# motor.net
KiCad netlist of a schematic drawn in EAGLE
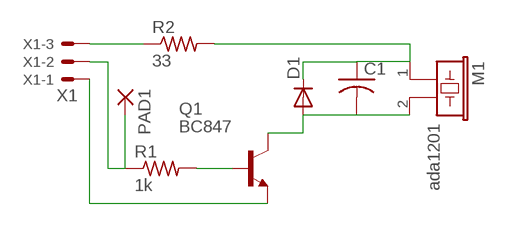
[diagram p0: schematic, sheet 1]

(export (version "E")
  (design (tool "Eeschema 10.0.6"))
  (components
    (comp (ref "C1")
      (value "C-USC0603")
      (footprint "eagle-import:C0603")
      (libsource (lib "eagle-import") (part "C-USC0603"))
    )
    (comp (ref "D1")
      (value "DIODE-DO214AC")
      (footprint "eagle-import:DO214AC")
      (libsource (lib "eagle-import") (part "DIODE-DO214AC"))
    )
    (comp (ref "M1")
      (value "ada1201")
      (footprint "eagle-import:B_C11L")
      (libsource (lib "eagle-import") (part "B/C11L"))
    )
    (comp (ref "PAD1")
      (value "1,6/0,8")
      (footprint "eagle-import:1,6_0,8")
      (libsource (lib "eagle-import") (part "1,6/0,8"))
    )
    (comp (ref "Q1")
      (value "BC847")
      (footprint "eagle-import:SOT23")
      (libsource (lib "eagle-import") (part "BCX70SMD"))
    )
    (comp (ref "R1")
      (value "1k")
      (footprint "eagle-import:R0805")
      (libsource (lib "eagle-import") (part "R-US_R0805"))
    )
    (comp (ref "R2")
      (value "33")
      (footprint "eagle-import:R0805")
      (libsource (lib "eagle-import") (part "R-US_R0805"))
    )
    (comp (ref "X1")
      (value "X1")
      (footprint "eagle-import:22-23-2031")
      (fields (field (name "MF") "MOLEX") (field (name "MPN") "22-23-2031"))
      (libsource (lib "eagle-import") (part "22-23-2031"))
    )
  )
  (nets
    (net (code "1") (name "Net-(C1-Pad1)") (class "Default")
      (node (ref "C1") (pin "1") (pinfunction "1_1") (pintype "passive"))
      (node (ref "D1") (pin "C") (pinfunction "C_C") (pintype "passive"))
      (node (ref "M1") (pin "1") (pinfunction "1_1") (pintype "passive"))
      (node (ref "R2") (pin "2") (pinfunction "2_2") (pintype "passive"))
    )
    (net (code "2") (name "Net-(PAD1-P)") (class "Default")
      (node (ref "PAD1") (pin "1") (pinfunction "P_1") (pintype "passive"))
      (node (ref "R1") (pin "1") (pinfunction "1_1") (pintype "passive"))
      (node (ref "X1") (pin "2") (pinfunction "S_2") (pintype "passive"))
    )
    (net (code "3") (name "Net-(Q1-B)") (class "Default")
      (node (ref "Q1") (pin "1") (pinfunction "B_1") (pintype "passive"))
      (node (ref "R1") (pin "2") (pinfunction "2_2") (pintype "passive"))
    )
    (net (code "4") (name "Net-(Q1-C)") (class "Default")
      (node (ref "C1") (pin "2") (pinfunction "2_2") (pintype "passive"))
      (node (ref "D1") (pin "A") (pinfunction "A_A") (pintype "passive"))
      (node (ref "M1") (pin "2") (pinfunction "2_2") (pintype "passive"))
      (node (ref "Q1") (pin "3") (pinfunction "C_3") (pintype "passive"))
    )
    (net (code "5") (name "Net-(Q1-E)") (class "Default")
      (node (ref "Q1") (pin "2") (pinfunction "E_2") (pintype "passive"))
      (node (ref "X1") (pin "1") (pinfunction "S_1") (pintype "passive"))
    )
    (net (code "6") (name "Net-(X1C-S)") (class "Default")
      (node (ref "R2") (pin "1") (pinfunction "1_1") (pintype "passive"))
      (node (ref "X1") (pin "3") (pinfunction "S_3") (pintype "passive"))
    )
  )
)
